# psu1.net
KiCad netlist of a schematic drawn in EAGLE
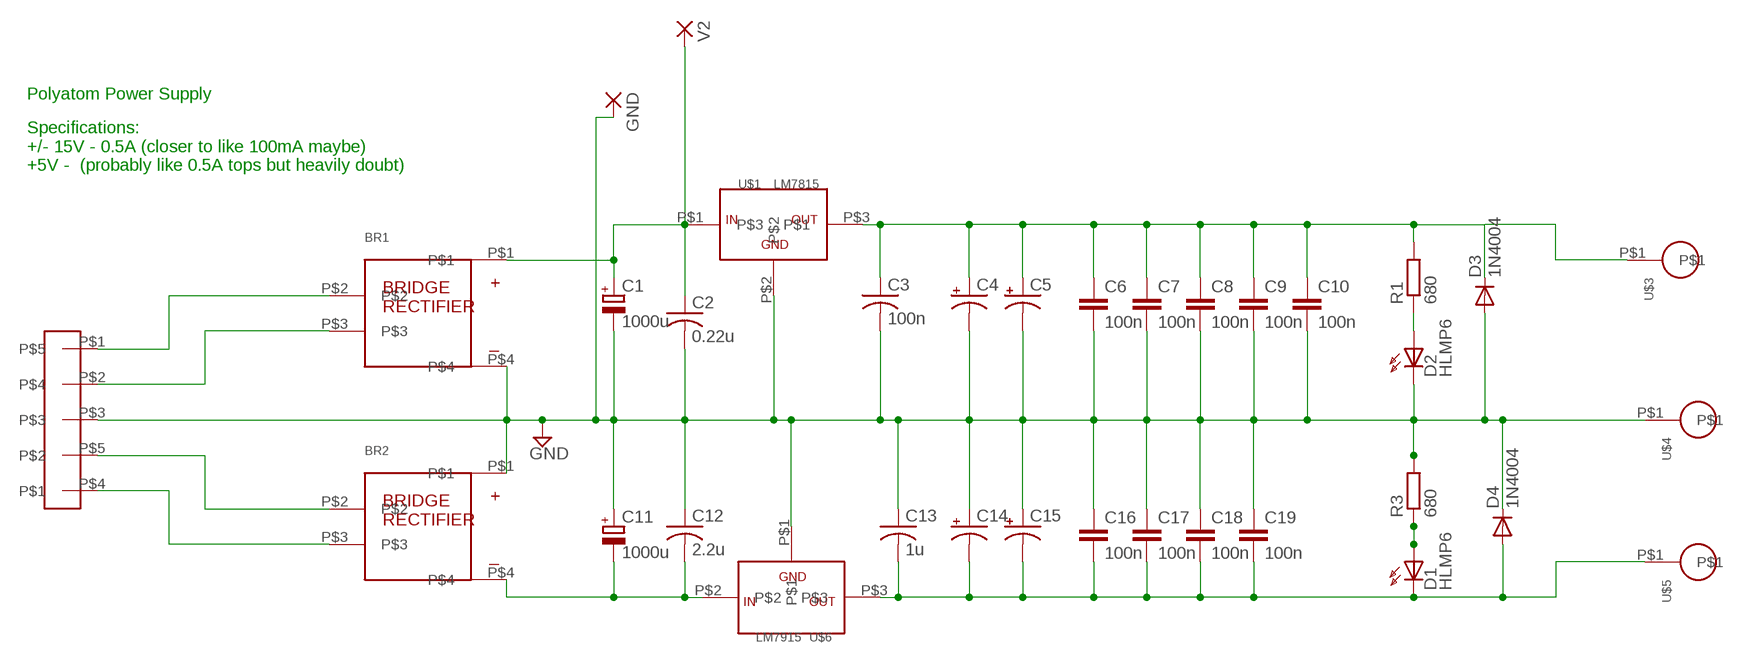
[diagram p0: schematic, sheet 1]

(export (version "E")
  (design (tool "Eeschema 10.0.6"))
  (components
    (comp (ref "BR1")
      (value "GBU4J")
      (footprint "eagle-import:SIL4")
      (libsource (lib "eagle-import") (part "GBU4J"))
    )
    (comp (ref "BR2")
      (value "GBU4J")
      (footprint "eagle-import:SIL4")
      (libsource (lib "eagle-import") (part "GBU4J"))
    )
    (comp (ref "C1")
      (value "1000u")
      (footprint "eagle-import:E5-13")
      (libsource (lib "eagle-import") (part "CPOL-EUE5-13"))
    )
    (comp (ref "C2")
      (value "0.22u")
      (footprint "eagle-import:C1206")
      (libsource (lib "eagle-import") (part "C-USC1206"))
    )
    (comp (ref "C3")
      (value "100n")
      (footprint "eagle-import:C1206")
      (libsource (lib "eagle-import") (part "C-USC1206"))
    )
    (comp (ref "C4")
      (value "CPOL-USTT2D5")
      (footprint "eagle-import:TT2D5")
      (libsource (lib "eagle-import") (part "CPOL-USTT2D5"))
    )
    (comp (ref "C5")
      (value "CPOL-USTT2D5")
      (footprint "eagle-import:TT2D5")
      (libsource (lib "eagle-import") (part "CPOL-USTT2D5"))
    )
    (comp (ref "C6")
      (value "100n")
      (footprint "eagle-import:C1206")
      (libsource (lib "eagle-import") (part "CC1206"))
    )
    (comp (ref "C7")
      (value "100n")
      (footprint "eagle-import:C1206")
      (libsource (lib "eagle-import") (part "CC1206"))
    )
    (comp (ref "C8")
      (value "100n")
      (footprint "eagle-import:C1206")
      (libsource (lib "eagle-import") (part "CC1206"))
    )
    (comp (ref "C9")
      (value "100n")
      (footprint "eagle-import:C1206")
      (libsource (lib "eagle-import") (part "CC1206"))
    )
    (comp (ref "C10")
      (value "100n")
      (footprint "eagle-import:C1206")
      (libsource (lib "eagle-import") (part "CC1206"))
    )
    (comp (ref "C11")
      (value "1000u")
      (footprint "eagle-import:E5-13")
      (libsource (lib "eagle-import") (part "CPOL-EUE5-13"))
    )
    (comp (ref "C12")
      (value "2.2u")
      (footprint "eagle-import:C1206")
      (libsource (lib "eagle-import") (part "C-USC1206"))
    )
    (comp (ref "C13")
      (value "1u")
      (footprint "eagle-import:C1206")
      (libsource (lib "eagle-import") (part "C-USC1206"))
    )
    (comp (ref "C14")
      (value "CPOL-USTT2D5")
      (footprint "eagle-import:TT2D5")
      (libsource (lib "eagle-import") (part "CPOL-USTT2D5"))
    )
    (comp (ref "C15")
      (value "CPOL-USTT2D5")
      (footprint "eagle-import:TT2D5")
      (libsource (lib "eagle-import") (part "CPOL-USTT2D5"))
    )
    (comp (ref "C16")
      (value "100n")
      (footprint "eagle-import:C1206")
      (libsource (lib "eagle-import") (part "CC1206"))
    )
    (comp (ref "C17")
      (value "100n")
      (footprint "eagle-import:C1206")
      (libsource (lib "eagle-import") (part "CC1206"))
    )
    (comp (ref "C18")
      (value "100n")
      (footprint "eagle-import:C1206")
      (libsource (lib "eagle-import") (part "CC1206"))
    )
    (comp (ref "C19")
      (value "100n")
      (footprint "eagle-import:C1206")
      (libsource (lib "eagle-import") (part "CC1206"))
    )
    (comp (ref "D1")
      (value "HLMP6")
      (footprint "eagle-import:HLMP6")
      (fields (field (name "MF") "AGILENT TECHNOLOGIES") (field (name "MPN") "HLMP-6500"))
      (libsource (lib "eagle-import") (part "HLMP6"))
    )
    (comp (ref "D2")
      (value "HLMP6")
      (footprint "eagle-import:HLMP6")
      (fields (field (name "MF") "AGILENT TECHNOLOGIES") (field (name "MPN") "HLMP-6500"))
      (libsource (lib "eagle-import") (part "HLMP6"))
    )
    (comp (ref "D3")
      (value "1N4004")
      (footprint "eagle-import:DO41-10")
      (libsource (lib "eagle-import") (part "1N4004"))
    )
    (comp (ref "D4")
      (value "1N4004")
      (footprint "eagle-import:DO41-10")
      (libsource (lib "eagle-import") (part "1N4004"))
    )
    (comp (ref "GND")
      (value "3,81/1,1")
      (footprint "eagle-import:3,81_1,1")
      (libsource (lib "eagle-import") (part "3,81/1,1"))
    )
    (comp (ref "R1")
      (value "680")
      (footprint "eagle-import:0207_10")
      (libsource (lib "eagle-import") (part "R0207/10"))
    )
    (comp (ref "R3")
      (value "680")
      (footprint "eagle-import:0207_10")
      (libsource (lib "eagle-import") (part "R0207/10"))
    )
    (comp (ref "U$1")
      (value "LM7815")
      (footprint "eagle-import:TO-220")
      (libsource (lib "eagle-import") (part "LM7815"))
    )
    (comp (ref "U$3")
      (value "BANANA")
      (footprint "eagle-import:BANANA")
      (libsource (lib "eagle-import") (part "BANANA"))
    )
    (comp (ref "U$4")
      (value "BANANA")
      (footprint "eagle-import:BANANA")
      (libsource (lib "eagle-import") (part "BANANA"))
    )
    (comp (ref "U$5")
      (value "BANANA")
      (footprint "eagle-import:BANANA")
      (libsource (lib "eagle-import") (part "BANANA"))
    )
    (comp (ref "U$6")
      (value "LM7915")
      (footprint "eagle-import:TO-220")
      (libsource (lib "eagle-import") (part "LM7915"))
    )
    (comp (ref "U$8")
      (value "TERMINALBLOCK")
      (footprint "eagle-import:TERMINALBLOKC")
      (libsource (lib "eagle-import") (part "TERMINALBLOCK"))
    )
    (comp (ref "V2")
      (value "3,81/1,1")
      (footprint "eagle-import:3,81_1,1")
      (libsource (lib "eagle-import") (part "3,81/1,1"))
    )
  )
  (nets
    (net (code "1") (name "GND") (class "Default")
      (node (ref "BR1") (pin "P$4") (pinfunction "P$4_P$4") (pintype "bidirectional"))
      (node (ref "BR2") (pin "P$1") (pinfunction "P$1_P$1") (pintype "bidirectional"))
      (node (ref "C1") (pin "-") (pinfunction "-_-") (pintype "passive"))
      (node (ref "C10") (pin "2") (pinfunction "2_2") (pintype "passive"))
      (node (ref "C11") (pin "+") (pinfunction "+_+") (pintype "passive"))
      (node (ref "C12") (pin "1") (pinfunction "1_1") (pintype "passive"))
      (node (ref "C13") (pin "1") (pinfunction "1_1") (pintype "passive"))
      (node (ref "C14") (pin "+") (pinfunction "+_+") (pintype "passive"))
      (node (ref "C15") (pin "+") (pinfunction "+_+") (pintype "passive"))
      (node (ref "C16") (pin "1") (pinfunction "1_1") (pintype "passive"))
      (node (ref "C17") (pin "1") (pinfunction "1_1") (pintype "passive"))
      (node (ref "C18") (pin "1") (pinfunction "1_1") (pintype "passive"))
      (node (ref "C19") (pin "1") (pinfunction "1_1") (pintype "passive"))
      (node (ref "C2") (pin "2") (pinfunction "2_2") (pintype "passive"))
      (node (ref "C3") (pin "2") (pinfunction "2_2") (pintype "passive"))
      (node (ref "C4") (pin "-") (pinfunction "-_-") (pintype "passive"))
      (node (ref "C5") (pin "-") (pinfunction "-_-") (pintype "passive"))
      (node (ref "C6") (pin "2") (pinfunction "2_2") (pintype "passive"))
      (node (ref "C7") (pin "2") (pinfunction "2_2") (pintype "passive"))
      (node (ref "C8") (pin "2") (pinfunction "2_2") (pintype "passive"))
      (node (ref "C9") (pin "2") (pinfunction "2_2") (pintype "passive"))
      (node (ref "D2") (pin "K") (pinfunction "K_K") (pintype "passive"))
      (node (ref "D3") (pin "A") (pinfunction "A_A") (pintype "passive"))
      (node (ref "D4") (pin "C") (pinfunction "C_C") (pintype "passive"))
      (node (ref "GND") (pin "1") (pinfunction "P_1") (pintype "passive"))
      (node (ref "R3") (pin "2") (pinfunction "2_2") (pintype "passive"))
      (node (ref "U$1") (pin "P$2") (pinfunction "P$2_P$2") (pintype "bidirectional"))
      (node (ref "U$4") (pin "P$1") (pinfunction "P$1_P$1") (pintype "bidirectional"))
      (node (ref "U$6") (pin "P$1") (pinfunction "P$1_P$1") (pintype "bidirectional"))
      (node (ref "U$8") (pin "P$3") (pinfunction "P$3_P$3") (pintype "bidirectional"))
    )
    (net (code "2") (name "Net-(BR2-PadP$4)") (class "Default")
      (node (ref "BR2") (pin "P$4") (pinfunction "P$4_P$4") (pintype "bidirectional"))
      (node (ref "C11") (pin "-") (pinfunction "-_-") (pintype "passive"))
      (node (ref "C12") (pin "2") (pinfunction "2_2") (pintype "passive"))
      (node (ref "U$6") (pin "P$2") (pinfunction "P$2_P$2") (pintype "bidirectional"))
    )
    (net (code "3") (name "Net-(C13-Pad2)") (class "Default")
      (node (ref "C13") (pin "2") (pinfunction "2_2") (pintype "passive"))
      (node (ref "C14") (pin "-") (pinfunction "-_-") (pintype "passive"))
      (node (ref "C15") (pin "-") (pinfunction "-_-") (pintype "passive"))
      (node (ref "C16") (pin "2") (pinfunction "2_2") (pintype "passive"))
      (node (ref "C17") (pin "2") (pinfunction "2_2") (pintype "passive"))
      (node (ref "C18") (pin "2") (pinfunction "2_2") (pintype "passive"))
      (node (ref "C19") (pin "2") (pinfunction "2_2") (pintype "passive"))
      (node (ref "D1") (pin "K") (pinfunction "K_K") (pintype "passive"))
      (node (ref "D4") (pin "A") (pinfunction "A_A") (pintype "passive"))
      (node (ref "U$5") (pin "P$1") (pinfunction "P$1_P$1") (pintype "bidirectional"))
      (node (ref "U$6") (pin "P$3") (pinfunction "P$3_P$3") (pintype "bidirectional"))
    )
    (net (code "4") (name "Net-(D1-PadA)") (class "Default")
      (node (ref "D1") (pin "A") (pinfunction "A_A") (pintype "passive"))
      (node (ref "R3") (pin "1") (pinfunction "1_1") (pintype "passive"))
    )
    (net (code "5") (name "Net-(D2-PadA)") (class "Default")
      (node (ref "D2") (pin "A") (pinfunction "A_A") (pintype "passive"))
      (node (ref "R1") (pin "1") (pinfunction "1_1") (pintype "passive"))
    )
    (net (code "6") (name "Net-(U$1-P$1)") (class "Default")
      (node (ref "C10") (pin "1") (pinfunction "1_1") (pintype "passive"))
      (node (ref "C3") (pin "1") (pinfunction "1_1") (pintype "passive"))
      (node (ref "C4") (pin "+") (pinfunction "+_+") (pintype "passive"))
      (node (ref "C5") (pin "+") (pinfunction "+_+") (pintype "passive"))
      (node (ref "C6") (pin "1") (pinfunction "1_1") (pintype "passive"))
      (node (ref "C7") (pin "1") (pinfunction "1_1") (pintype "passive"))
      (node (ref "C8") (pin "1") (pinfunction "1_1") (pintype "passive"))
      (node (ref "C9") (pin "1") (pinfunction "1_1") (pintype "passive"))
      (node (ref "D3") (pin "C") (pinfunction "C_C") (pintype "passive"))
      (node (ref "R1") (pin "2") (pinfunction "2_2") (pintype "passive"))
      (node (ref "U$1") (pin "P$3") (pinfunction "P$1_P$3") (pintype "bidirectional"))
      (node (ref "U$3") (pin "P$1") (pinfunction "P$1_P$1") (pintype "bidirectional"))
    )
    (net (code "7") (name "Net-(U$1-P$3)") (class "Default")
      (node (ref "BR1") (pin "P$1") (pinfunction "P$1_P$1") (pintype "bidirectional"))
      (node (ref "C1") (pin "+") (pinfunction "+_+") (pintype "passive"))
      (node (ref "C2") (pin "1") (pinfunction "1_1") (pintype "passive"))
      (node (ref "U$1") (pin "P$1") (pinfunction "P$3_P$1") (pintype "bidirectional"))
      (node (ref "V2") (pin "1") (pinfunction "P_1") (pintype "passive"))
    )
    (net (code "8") (name "Net-(U$8-P$1)") (class "Default")
      (node (ref "BR2") (pin "P$3") (pinfunction "P$3_P$3") (pintype "bidirectional"))
      (node (ref "U$8") (pin "P$4") (pinfunction "P$1_P$4") (pintype "bidirectional"))
    )
    (net (code "9") (name "Net-(U$8-P$2)") (class "Default")
      (node (ref "BR2") (pin "P$2") (pinfunction "P$2_P$2") (pintype "bidirectional"))
      (node (ref "U$8") (pin "P$5") (pinfunction "P$2_P$5") (pintype "bidirectional"))
    )
    (net (code "10") (name "Net-(U$8-P$4)") (class "Default")
      (node (ref "BR1") (pin "P$3") (pinfunction "P$3_P$3") (pintype "bidirectional"))
      (node (ref "U$8") (pin "P$2") (pinfunction "P$4_P$2") (pintype "bidirectional"))
    )
    (net (code "11") (name "Net-(U$8-P$5)") (class "Default")
      (node (ref "BR1") (pin "P$2") (pinfunction "P$2_P$2") (pintype "bidirectional"))
      (node (ref "U$8") (pin "P$1") (pinfunction "P$5_P$1") (pintype "bidirectional"))
    )
  )
)
